# sch_ma.net
KiCad netlist of a schematic drawn in EAGLE
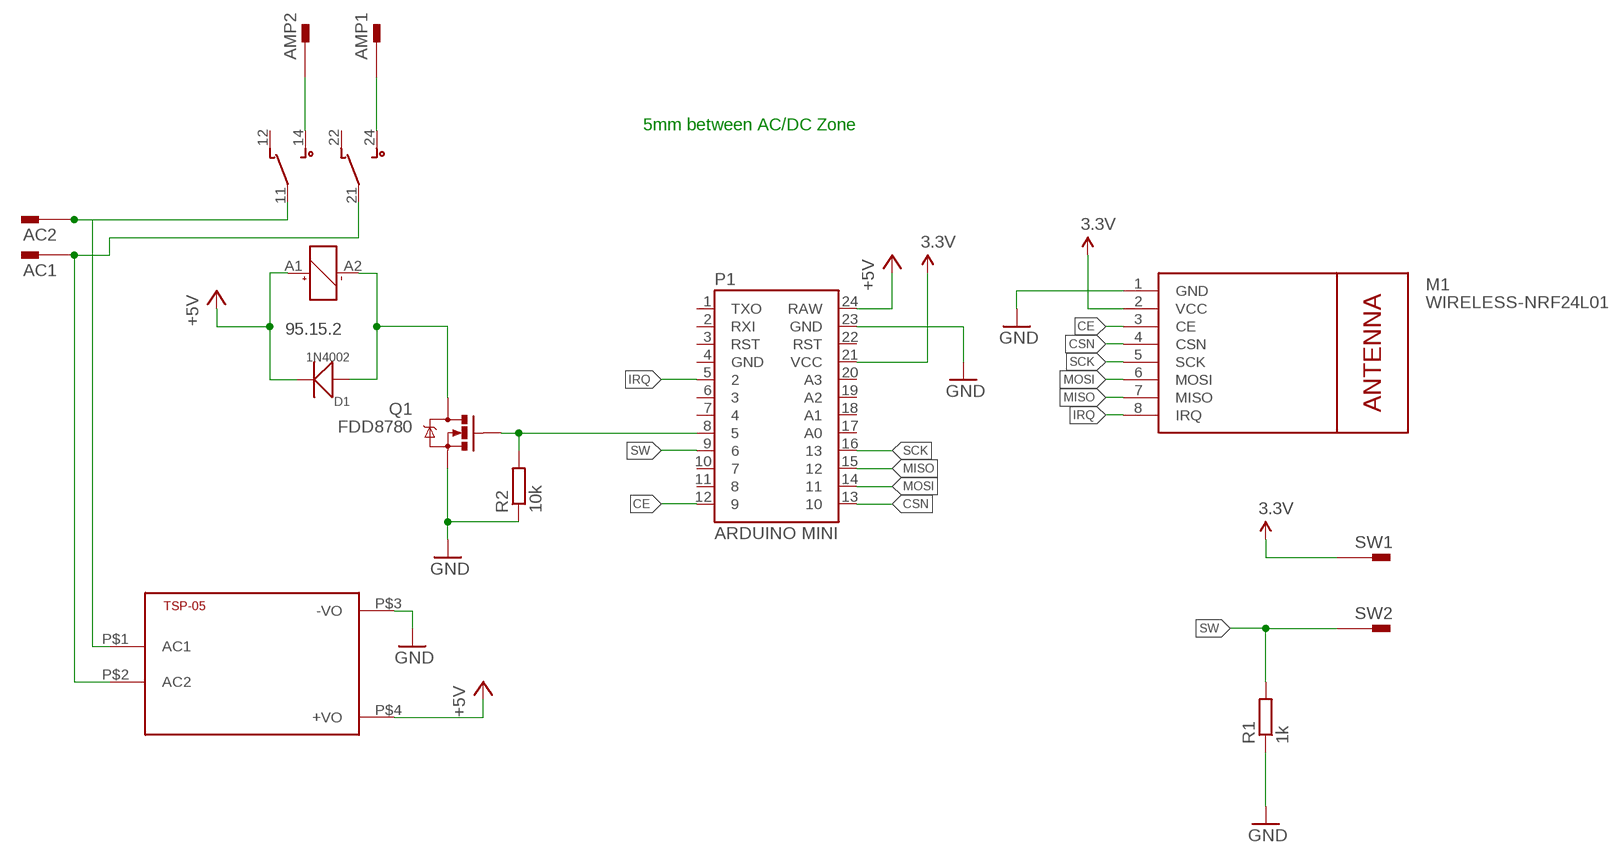
[diagram p0: schematic, sheet 1]

(export (version "E")
  (design (tool "Eeschema 10.0.6"))
  (components
    (comp (ref "AC1")
      (value "PIN2F061.100")
      (footprint "eagle-import:F061.100")
      (libsource (lib "eagle-import") (part "PIN2F061.100"))
    )
    (comp (ref "AC2")
      (value "PIN2F061.100")
      (footprint "eagle-import:F061.100")
      (libsource (lib "eagle-import") (part "PIN2F061.100"))
    )
    (comp (ref "AMP1")
      (value "PIN2F061.100")
      (footprint "eagle-import:F061.100")
      (libsource (lib "eagle-import") (part "PIN2F061.100"))
    )
    (comp (ref "AMP2")
      (value "PIN2F061.100")
      (footprint "eagle-import:F061.100")
      (libsource (lib "eagle-import") (part "PIN2F061.100"))
    )
    (comp (ref "D1")
      (value "1N4002")
      (footprint "eagle-import:DO-41")
      (fields (field (name "MPN") "1N4001"))
      (libsource (lib "eagle-import") (part "DIP-DIODE-50V-1A-1N4001(DO-41)"))
    )
    (comp (ref "M1")
      (value "WIRELESS-NRF24L01")
      (footprint "eagle-import:WIRELESS-NRF24L01")
      (libsource (lib "eagle-import") (part "WIRELESS-NRF24L01"))
    )
    (comp (ref "P1")
      (value "ARDUINO MINI")
      (footprint "eagle-import:ARDUINO_MINI")
      (libsource (lib "eagle-import") (part "ARDUINO_MINI"))
    )
    (comp (ref "Q1")
      (value "FDD8780")
      (footprint "eagle-import:DPAK")
      (libsource (lib "eagle-import") (part "MOSFET-NCHANNELFDD8780"))
    )
    (comp (ref "R1")
      (value "1k")
      (footprint "eagle-import:0207_10")
      (libsource (lib "eagle-import") (part "R-EU_0207/10"))
    )
    (comp (ref "R2")
      (value "10k")
      (footprint "eagle-import:0207_10")
      (libsource (lib "eagle-import") (part "R-EU_0207/10"))
    )
    (comp (ref "RL1")
      (value "95.15.2")
      (footprint "eagle-import:95.15.2")
      (libsource (lib "eagle-import") (part "95.15.2"))
    )
    (comp (ref "SW1")
      (value "PIN2F061.100")
      (footprint "eagle-import:F061.100")
      (libsource (lib "eagle-import") (part "PIN2F061.100"))
    )
    (comp (ref "SW2")
      (value "PIN2F061.100")
      (footprint "eagle-import:F061.100")
      (libsource (lib "eagle-import") (part "PIN2F061.100"))
    )
    (comp (ref "TSP-05")
      (value "HKLPM01")
      (footprint "eagle-import:HKLPM01")
      (libsource (lib "eagle-import") (part "HKLPM01"))
    )
  )
  (nets
    (net (code "1") (name "+5V") (class "Default")
      (node (ref "D1") (pin "2") (pinfunction "-_2") (pintype "passive"))
      (node (ref "P1") (pin "24") (pinfunction "RAW_24") (pintype "bidirectional"))
      (node (ref "RL1") (pin "A1") (pinfunction "A1_A1") (pintype "passive"))
      (node (ref "TSP-05") (pin "P$4") (pinfunction "+VO_P$4") (pintype "bidirectional"))
    )
    (net (code "2") (name "3.3V") (class "Default")
      (node (ref "M1") (pin "2") (pinfunction "VCC_2") (pintype "power_in"))
      (node (ref "P1") (pin "21") (pinfunction "VCC_21") (pintype "bidirectional"))
      (node (ref "SW1") (pin "A1") (pinfunction "1_A1") (pintype "passive"))
      (node (ref "SW1") (pin "A2") (pinfunction "1_A2") (pintype "passive"))
    )
    (net (code "3") (name "CE") (class "Default")
      (node (ref "M1") (pin "3") (pinfunction "CE_3") (pintype "bidirectional"))
      (node (ref "P1") (pin "12") (pinfunction "9_12") (pintype "bidirectional"))
    )
    (net (code "4") (name "CSN") (class "Default")
      (node (ref "M1") (pin "4") (pinfunction "CSN_4") (pintype "bidirectional"))
      (node (ref "P1") (pin "13") (pinfunction "10_13") (pintype "bidirectional"))
    )
    (net (code "5") (name "GND") (class "Default")
      (node (ref "M1") (pin "1") (pinfunction "GND_1") (pintype "power_in"))
      (node (ref "P1") (pin "23") (pinfunction "GND_23") (pintype "bidirectional"))
      (node (ref "Q1") (pin "3") (pinfunction "S_3") (pintype "passive"))
      (node (ref "R1") (pin "1") (pinfunction "1_1") (pintype "passive"))
      (node (ref "R2") (pin "1") (pinfunction "1_1") (pintype "passive"))
      (node (ref "TSP-05") (pin "P$3") (pinfunction "-VO_P$3") (pintype "bidirectional"))
    )
    (net (code "6") (name "IRQ") (class "Default")
      (node (ref "M1") (pin "8") (pinfunction "IRQ_8") (pintype "bidirectional"))
      (node (ref "P1") (pin "5") (pinfunction "2_5") (pintype "bidirectional"))
    )
    (net (code "7") (name "MISO") (class "Default")
      (node (ref "M1") (pin "7") (pinfunction "MISO_7") (pintype "bidirectional"))
      (node (ref "P1") (pin "15") (pinfunction "12_15") (pintype "bidirectional"))
    )
    (net (code "8") (name "MOSI") (class "Default")
      (node (ref "M1") (pin "6") (pinfunction "MOSI_6") (pintype "bidirectional"))
      (node (ref "P1") (pin "14") (pinfunction "11_14") (pintype "bidirectional"))
    )
    (net (code "9") (name "Net-(AMP1-1-PadA1)") (class "Default")
      (node (ref "AMP1") (pin "A1") (pinfunction "1_A1") (pintype "passive"))
      (node (ref "AMP1") (pin "A2") (pinfunction "1_A2") (pintype "passive"))
      (node (ref "RL1") (pin "24") (pinfunction "24_24") (pintype "passive"))
    )
    (net (code "10") (name "Net-(AMP2-1-PadA1)") (class "Default")
      (node (ref "AMP2") (pin "A1") (pinfunction "1_A1") (pintype "passive"))
      (node (ref "AMP2") (pin "A2") (pinfunction "1_A2") (pintype "passive"))
      (node (ref "RL1") (pin "14") (pinfunction "14_14") (pintype "passive"))
    )
    (net (code "11") (name "Net-(D1-+)") (class "Default")
      (node (ref "D1") (pin "1") (pinfunction "+_1") (pintype "passive"))
      (node (ref "Q1") (pin "4") (pinfunction "D_4") (pintype "passive"))
      (node (ref "RL1") (pin "A2") (pinfunction "A2_A2") (pintype "passive"))
    )
    (net (code "12") (name "Net-(P1-5)") (class "Default")
      (node (ref "P1") (pin "8") (pinfunction "5_8") (pintype "bidirectional"))
      (node (ref "Q1") (pin "1") (pinfunction "G_1") (pintype "passive"))
      (node (ref "R2") (pin "2") (pinfunction "2_2") (pintype "passive"))
    )
    (net (code "13") (name "Net-(TSP-05-AC1)") (class "Default")
      (node (ref "AC2") (pin "A1") (pinfunction "1_A1") (pintype "passive"))
      (node (ref "AC2") (pin "A2") (pinfunction "1_A2") (pintype "passive"))
      (node (ref "RL1") (pin "11") (pinfunction "11_11") (pintype "passive"))
      (node (ref "TSP-05") (pin "P$1") (pinfunction "AC1_P$1") (pintype "bidirectional"))
    )
    (net (code "14") (name "Net-(TSP-05-AC2)") (class "Default")
      (node (ref "AC1") (pin "A1") (pinfunction "1_A1") (pintype "passive"))
      (node (ref "AC1") (pin "A2") (pinfunction "1_A2") (pintype "passive"))
      (node (ref "RL1") (pin "21") (pinfunction "21_21") (pintype "passive"))
      (node (ref "TSP-05") (pin "P$2") (pinfunction "AC2_P$2") (pintype "bidirectional"))
    )
    (net (code "15") (name "SCK") (class "Default")
      (node (ref "M1") (pin "5") (pinfunction "SCK_5") (pintype "bidirectional"))
      (node (ref "P1") (pin "16") (pinfunction "13_16") (pintype "bidirectional"))
    )
    (net (code "16") (name "SW") (class "Default")
      (node (ref "P1") (pin "9") (pinfunction "6_9") (pintype "bidirectional"))
      (node (ref "R1") (pin "2") (pinfunction "2_2") (pintype "passive"))
      (node (ref "SW2") (pin "A1") (pinfunction "1_A1") (pintype "passive"))
      (node (ref "SW2") (pin "A2") (pinfunction "1_A2") (pintype "passive"))
    )
    (net (code "17") (name "unconnected-(P1-3-Pad6)") (class "Default")
      (node (ref "P1") (pin "6") (pinfunction "3_6") (pintype "bidirectional"))
    )
    (net (code "18") (name "unconnected-(P1-4-Pad7)") (class "Default")
      (node (ref "P1") (pin "7") (pinfunction "4_7") (pintype "bidirectional"))
    )
    (net (code "19") (name "unconnected-(P1-7-Pad10)") (class "Default")
      (node (ref "P1") (pin "10") (pinfunction "7_10") (pintype "bidirectional"))
    )
    (net (code "20") (name "unconnected-(P1-8-Pad11)") (class "Default")
      (node (ref "P1") (pin "11") (pinfunction "8_11") (pintype "bidirectional"))
    )
    (net (code "21") (name "unconnected-(P1-A0-Pad17)") (class "Default")
      (node (ref "P1") (pin "17") (pinfunction "A0_17") (pintype "bidirectional"))
    )
    (net (code "22") (name "unconnected-(P1-A1-Pad18)") (class "Default")
      (node (ref "P1") (pin "18") (pinfunction "A1_18") (pintype "bidirectional"))
    )
    (net (code "23") (name "unconnected-(P1-A2-Pad19)") (class "Default")
      (node (ref "P1") (pin "19") (pinfunction "A2_19") (pintype "bidirectional"))
    )
    (net (code "24") (name "unconnected-(P1-A3-Pad20)") (class "Default")
      (node (ref "P1") (pin "20") (pinfunction "A3_20") (pintype "bidirectional"))
    )
    (net (code "25") (name "unconnected-(P1-GND-Pad4)") (class "Default")
      (node (ref "P1") (pin "4") (pinfunction "GND_4") (pintype "bidirectional"))
    )
    (net (code "26") (name "unconnected-(P1-RST-Pad3)") (class "Default")
      (node (ref "P1") (pin "3") (pinfunction "RST_3") (pintype "bidirectional"))
    )
    (net (code "27") (name "unconnected-(P1-RST-Pad22)") (class "Default")
      (node (ref "P1") (pin "22") (pinfunction "RST_22") (pintype "bidirectional"))
    )
    (net (code "28") (name "unconnected-(P1-RXI-Pad2)") (class "Default")
      (node (ref "P1") (pin "2") (pinfunction "RXI_2") (pintype "bidirectional"))
    )
    (net (code "29") (name "unconnected-(P1-TXO-Pad1)") (class "Default")
      (node (ref "P1") (pin "1") (pinfunction "TXO_1") (pintype "bidirectional"))
    )
    (net (code "30") (name "unconnected-(RL1-Pad12)") (class "Default")
      (node (ref "RL1") (pin "12") (pinfunction "12_12") (pintype "passive"))
    )
    (net (code "31") (name "unconnected-(RL1-Pad22)") (class "Default")
      (node (ref "RL1") (pin "22") (pinfunction "22_22") (pintype "passive"))
    )
  )
)
